# buzz.net
KiCad netlist of a schematic drawn in EAGLE
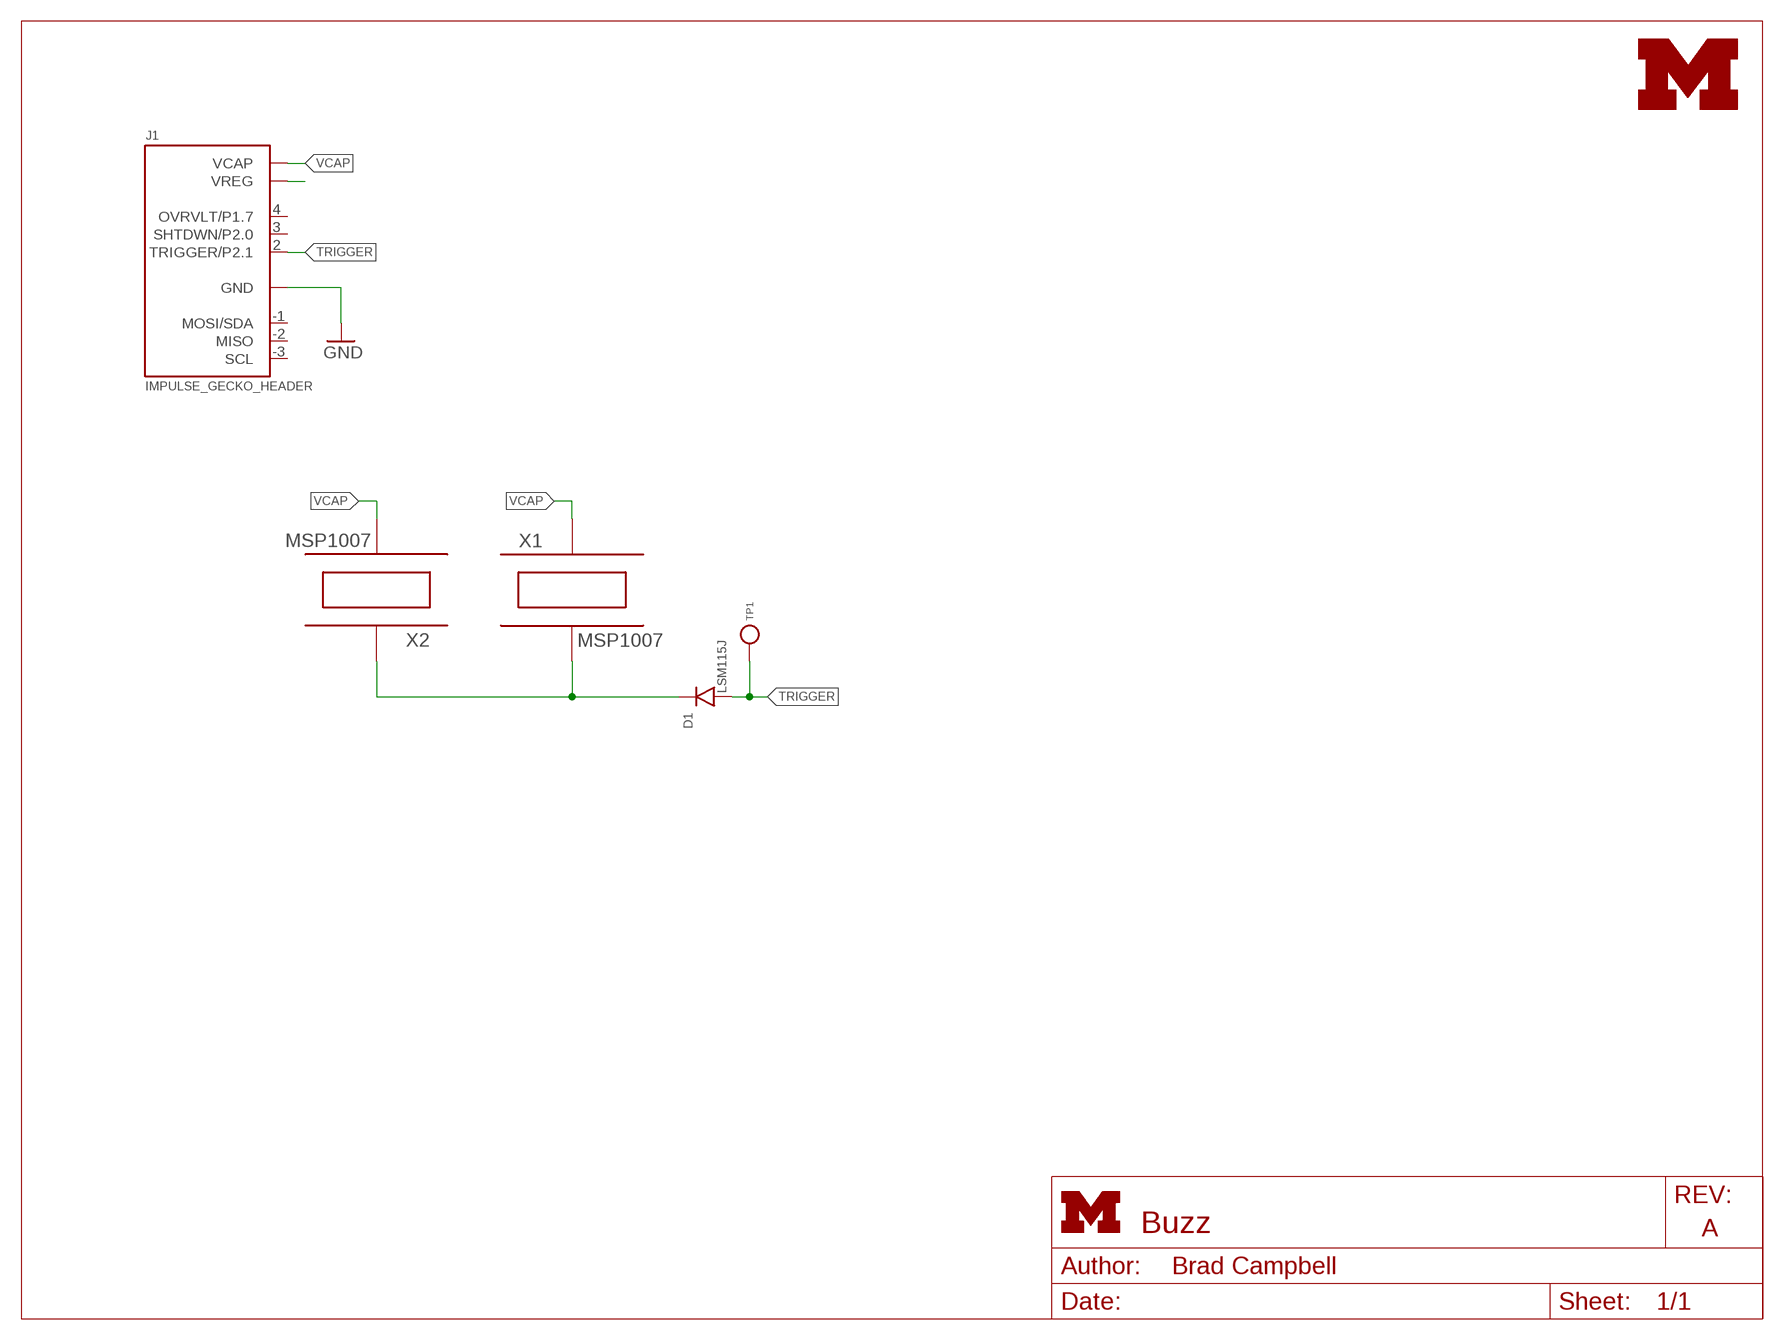
[diagram p0: schematic, sheet 1]

(export (version "E")
  (design (tool "Eeschema 10.0.6"))
  (components
    (comp (ref "D1")
      (value "LSM115J")
      (footprint "eagle-import:D0-214BA")
      (libsource (lib "eagle-import") (part "LSM115J"))
    )
    (comp (ref "J1")
      (value "IMPULSE_GECKO_HEADER")
      (footprint "eagle-import:HEADER1X9_0.05IN")
      (libsource (lib "eagle-import") (part "IMPULSE_GECKO_HEADER"))
    )
    (comp (ref "TP1")
      (value "TEST_POINT_0.040IN")
      (footprint "eagle-import:TESTPOINT_0.040IN")
      (libsource (lib "eagle-import") (part "TEST_POINT_0.040IN"))
    )
    (comp (ref "U$3")
      (value "UMICH_SOLID_SMALL+")
      (footprint "eagle-import:UMICH_SOLID_100MIL")
      (libsource (lib "eagle-import") (part "UMICH_SOLID_SMALL+"))
    )
    (comp (ref "X1")
      (value "MSP1007")
      (footprint "eagle-import:MSP1007")
      (libsource (lib "eagle-import") (part "MSP1007"))
    )
    (comp (ref "X2")
      (value "MSP1007")
      (footprint "eagle-import:MSP1007")
      (libsource (lib "eagle-import") (part "MSP1007"))
    )
  )
  (nets
    (net (code "1") (name "GND") (class "Default")
      (node (ref "J1") (pin "0") (pinfunction "GND_0") (pintype "bidirectional"))
    )
    (net (code "2") (name "Net-(D1-PadC)") (class "Default")
      (node (ref "D1") (pin "C") (pinfunction "C_C") (pintype "bidirectional"))
      (node (ref "X1") (pin "2") (pinfunction "2_2") (pintype "bidirectional"))
      (node (ref "X2") (pin "1") (pinfunction "1_1") (pintype "bidirectional"))
    )
    (net (code "3") (name "TRIGGER") (class "Default")
      (node (ref "D1") (pin "A") (pinfunction "A_A") (pintype "bidirectional"))
      (node (ref "J1") (pin "2") (pinfunction "TRIGGER/P2.1_2") (pintype "bidirectional"))
      (node (ref "TP1") (pin "TESTPOINT") (pinfunction "TESTPOINT_TESTPOINT") (pintype "bidirectional"))
    )
    (net (code "4") (name "VCAP") (class "Default")
      (node (ref "J1") (pin "5") (pinfunction "VCAP_5") (pintype "output"))
      (node (ref "X1") (pin "1") (pinfunction "1_1") (pintype "bidirectional"))
      (node (ref "X2") (pin "2") (pinfunction "2_2") (pintype "bidirectional"))
    )
    (net (code "5") (name "unconnected-(J1-MISO-Pad-2)") (class "Default")
      (node (ref "J1") (pin "-2") (pinfunction "MISO_-2") (pintype "bidirectional"))
    )
    (net (code "6") (name "unconnected-(J1-MOSI{slash}SDA-Pad-1)") (class "Default")
      (node (ref "J1") (pin "-1") (pinfunction "MOSI/SDA_-1") (pintype "bidirectional"))
    )
    (net (code "7") (name "unconnected-(J1-OVRVLT{slash}P1.7-Pad4)") (class "Default")
      (node (ref "J1") (pin "4") (pinfunction "OVRVLT/P1.7_4") (pintype "bidirectional"))
    )
    (net (code "8") (name "unconnected-(J1-SCL-Pad-3)") (class "Default")
      (node (ref "J1") (pin "-3") (pinfunction "SCL_-3") (pintype "bidirectional"))
    )
    (net (code "9") (name "unconnected-(J1-SHTDWN{slash}P2.0-Pad3)") (class "Default")
      (node (ref "J1") (pin "3") (pinfunction "SHTDWN/P2.0_3") (pintype "bidirectional"))
    )
    (net (code "10") (name "unconnected-(J1-VREG-Pad1)") (class "Default")
      (node (ref "J1") (pin "1") (pinfunction "VREG_1") (pintype "bidirectional"))
    )
  )
)
